# RCJ_OnStage2024_FC_drivers.net
KiCad netlist of a schematic drawn in Altium Designer
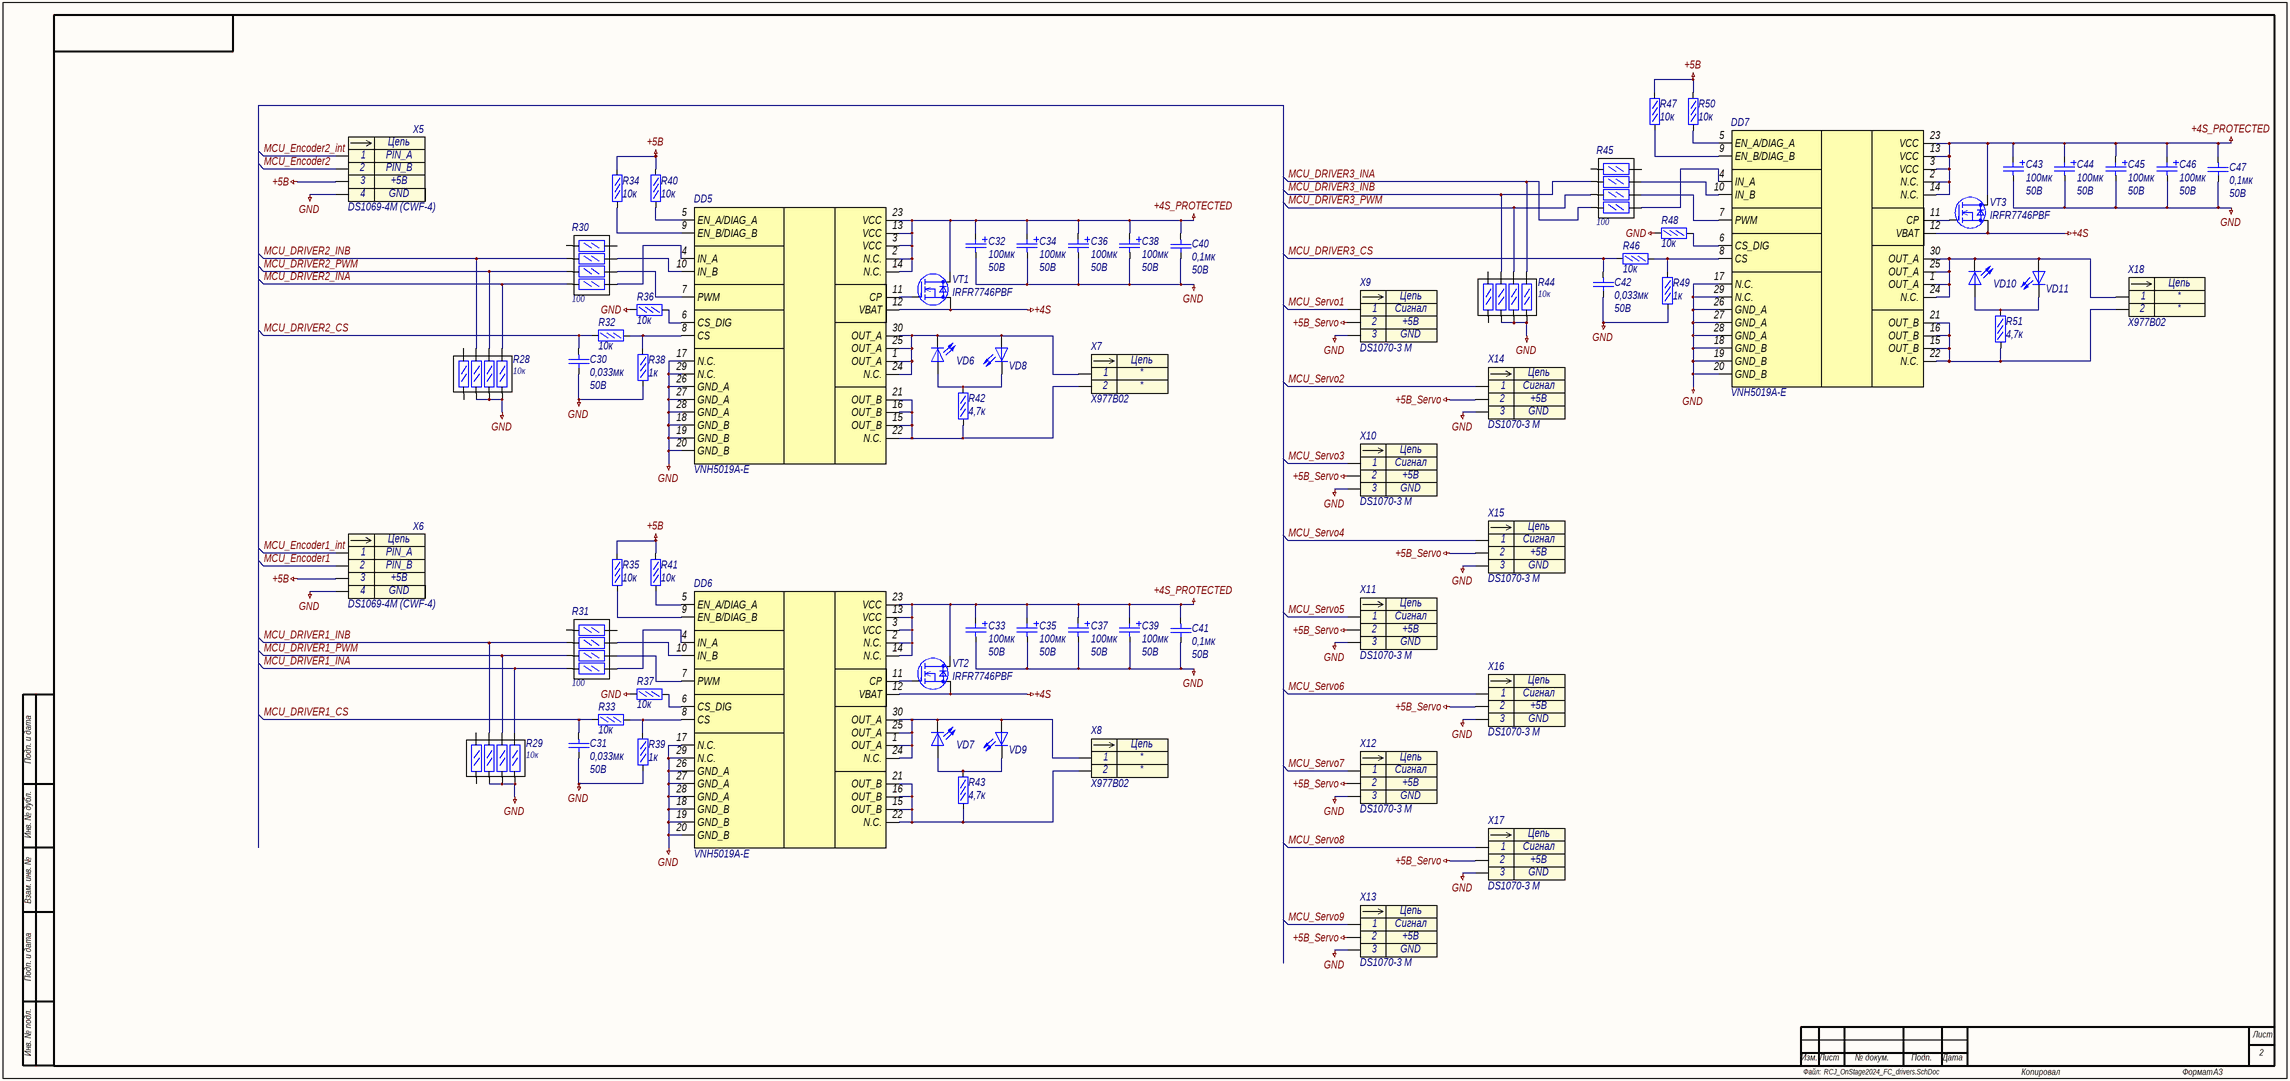
[diagram p0: RCJ_OnStage2024_FC_drivers.SchDoc]

(export (version "E")
  (design (tool "Eeschema 10.0.6"))
  (components
    (comp (ref "C30")
      (value "0,033мк")
      (footprint "C1206")
      (description "Конденсатор кер. 0,033мкФ 50В NP0")
      (fields (field (name "MANUFACTURER") "Murata") (field (name "VOLTAGE") "50В"))
      (libsource (lib "capacitors") (part "GRM3195C1H333J"))
    )
    (comp (ref "C31")
      (value "0,033мк")
      (footprint "C1206")
      (description "Конденсатор кер. 0,033мкФ 50В NP0")
      (fields (field (name "MANUFACTURER") "Murata") (field (name "VOLTAGE") "50В"))
      (libsource (lib "capacitors") (part "GRM3195C1H333J"))
    )
    (comp (ref "C32")
      (value "100мк")
      (footprint "CAPALUM_8x11.5_V")
      (description "Конденсатор эл.лит. алюм. 100мкФ 50В")
      (fields (field (name "MANUFACTURER") "EPCOS") (field (name "VOLTAGE") "50В"))
      (libsource (lib "capacitors") (part "B41858C6107M"))
    )
    (comp (ref "C33")
      (value "100мк")
      (footprint "CAPALUM_8x11.5_V")
      (description "Конденсатор эл.лит. алюм. 100мкФ 50В")
      (fields (field (name "MANUFACTURER") "EPCOS") (field (name "VOLTAGE") "50В"))
      (libsource (lib "capacitors") (part "B41858C6107M"))
    )
    (comp (ref "C34")
      (value "100мк")
      (footprint "CAPALUM_8x11.5_V")
      (description "Конденсатор эл.лит. алюм. 100мкФ 50В")
      (fields (field (name "MANUFACTURER") "EPCOS") (field (name "VOLTAGE") "50В"))
      (libsource (lib "capacitors") (part "B41858C6107M"))
    )
    (comp (ref "C35")
      (value "100мк")
      (footprint "CAPALUM_8x11.5_V")
      (description "Конденсатор эл.лит. алюм. 100мкФ 50В")
      (fields (field (name "MANUFACTURER") "EPCOS") (field (name "VOLTAGE") "50В"))
      (libsource (lib "capacitors") (part "B41858C6107M"))
    )
    (comp (ref "C36")
      (value "100мк")
      (footprint "CAPALUM_8x11.5_V")
      (description "Конденсатор эл.лит. алюм. 100мкФ 50В")
      (fields (field (name "MANUFACTURER") "EPCOS") (field (name "VOLTAGE") "50В"))
      (libsource (lib "capacitors") (part "B41858C6107M"))
    )
    (comp (ref "C37")
      (value "100мк")
      (footprint "CAPALUM_8x11.5_V")
      (description "Конденсатор эл.лит. алюм. 100мкФ 50В")
      (fields (field (name "MANUFACTURER") "EPCOS") (field (name "VOLTAGE") "50В"))
      (libsource (lib "capacitors") (part "B41858C6107M"))
    )
    (comp (ref "C38")
      (value "100мк")
      (footprint "CAPALUM_8x11.5_V")
      (description "Конденсатор эл.лит. алюм. 100мкФ 50В")
      (fields (field (name "MANUFACTURER") "EPCOS") (field (name "VOLTAGE") "50В"))
      (libsource (lib "capacitors") (part "B41858C6107M"))
    )
    (comp (ref "C39")
      (value "100мк")
      (footprint "CAPALUM_8x11.5_V")
      (description "Конденсатор эл.лит. алюм. 100мкФ 50В")
      (fields (field (name "MANUFACTURER") "EPCOS") (field (name "VOLTAGE") "50В"))
      (libsource (lib "capacitors") (part "B41858C6107M"))
    )
    (comp (ref "C40")
      (value "0,1мк")
      (footprint "C0603")
      (description "Конденсатор кер. 0,1мкФ 50В X7R")
      (fields (field (name "MANUFACTURER") "Murata") (field (name "VOLTAGE") "50В"))
      (libsource (lib "capacitors") (part "GRM188R71H104KA93D"))
    )
    (comp (ref "C41")
      (value "0,1мк")
      (footprint "C0603")
      (description "Конденсатор кер. 0,1мкФ 50В X7R")
      (fields (field (name "MANUFACTURER") "Murata") (field (name "VOLTAGE") "50В"))
      (libsource (lib "capacitors") (part "GRM188R71H104KA93D"))
    )
    (comp (ref "C42")
      (value "0,033мк")
      (footprint "C1206")
      (description "Конденсатор кер. 0,033мкФ 50В NP0")
      (fields (field (name "MANUFACTURER") "Murata") (field (name "VOLTAGE") "50В"))
      (libsource (lib "capacitors") (part "GRM3195C1H333J"))
    )
    (comp (ref "C43")
      (value "100мк")
      (footprint "CAPALUM_8x11.5_V")
      (description "Конденсатор эл.лит. алюм. 100мкФ 50В")
      (fields (field (name "MANUFACTURER") "EPCOS") (field (name "VOLTAGE") "50В"))
      (libsource (lib "capacitors") (part "B41858C6107M"))
    )
    (comp (ref "C44")
      (value "100мк")
      (footprint "CAPALUM_8x11.5_V")
      (description "Конденсатор эл.лит. алюм. 100мкФ 50В")
      (fields (field (name "MANUFACTURER") "EPCOS") (field (name "VOLTAGE") "50В"))
      (libsource (lib "capacitors") (part "B41858C6107M"))
    )
    (comp (ref "C45")
      (value "100мк")
      (footprint "CAPALUM_8x11.5_V")
      (description "Конденсатор эл.лит. алюм. 100мкФ 50В")
      (fields (field (name "MANUFACTURER") "EPCOS") (field (name "VOLTAGE") "50В"))
      (libsource (lib "capacitors") (part "B41858C6107M"))
    )
    (comp (ref "C46")
      (value "100мк")
      (footprint "CAPALUM_8x11.5_V")
      (description "Конденсатор эл.лит. алюм. 100мкФ 50В")
      (fields (field (name "MANUFACTURER") "EPCOS") (field (name "VOLTAGE") "50В"))
      (libsource (lib "capacitors") (part "B41858C6107M"))
    )
    (comp (ref "C47")
      (value "0,1мк")
      (footprint "C0603")
      (description "Конденсатор кер. 0,1мкФ 50В X7R")
      (fields (field (name "MANUFACTURER") "Murata") (field (name "VOLTAGE") "50В"))
      (libsource (lib "capacitors") (part "GRM188R71H104KA93D"))
    )
    (comp (ref "DD5") (value "VNH5019A-E") (footprint "SO-30") (libsource (lib "mcu") (part "VNH5019A-E")))
    (comp (ref "DD6") (value "VNH5019A-E") (footprint "SO-30") (libsource (lib "mcu") (part "VNH5019A-E")))
    (comp (ref "DD7") (value "VNH5019A-E") (footprint "SO-30") (libsource (lib "mcu") (part "VNH5019A-E")))
    (comp (ref "R28")
      (value "10к")
      (footprint "R0603x4")
      (description "Резисторы  0,125Вт")
      (libsource (lib "resistors") (part "Резисторная сборка х4 0,125 10кОм"))
    )
    (comp (ref "R29")
      (value "10к")
      (footprint "R0603x4")
      (description "Резисторы  0,125Вт")
      (libsource (lib "resistors") (part "Резисторная сборка х4 0,125 10кОм"))
    )
    (comp (ref "R30")
      (value "100")
      (footprint "R0603x4")
      (description "Резисторы  0,125Вт")
      (libsource (lib "resistors") (part "Резисторная сборка х4 0,125"))
    )
    (comp (ref "R31")
      (value "100")
      (footprint "R0603x4")
      (description "Резисторы  0,125Вт")
      (libsource (lib "resistors") (part "Резисторная сборка х4 0,125"))
    )
    (comp (ref "R32")
      (value "10к")
      (footprint "R0603")
      (description "Резистор 10кОм 0,063Вт 1%")
      (fields (field (name "MANUFACTURER") "YAGEO") (field (name "TOLERANCE") "1%"))
      (libsource (lib "resistors") (part "RC0603FR-0710KL"))
    )
    (comp (ref "R33")
      (value "10к")
      (footprint "R0603")
      (description "Резистор 10кОм 0,063Вт 1%")
      (fields (field (name "MANUFACTURER") "YAGEO") (field (name "TOLERANCE") "1%"))
      (libsource (lib "resistors") (part "RC0603FR-0710KL"))
    )
    (comp (ref "R34")
      (value "10к")
      (footprint "R0603")
      (description "Резистор 10кОм 0,063Вт 1%")
      (fields (field (name "MANUFACTURER") "YAGEO") (field (name "TOLERANCE") "1%"))
      (libsource (lib "") (part "RC0603FR-0710KL_1"))
    )
    (comp (ref "R35")
      (value "10к")
      (footprint "R0603")
      (description "Резистор 10кОм 0,063Вт 1%")
      (fields (field (name "MANUFACTURER") "YAGEO") (field (name "TOLERANCE") "1%"))
      (libsource (lib "") (part "RC0603FR-0710KL_1"))
    )
    (comp (ref "R36")
      (value "10к")
      (footprint "R0603")
      (description "Резистор 10кОм 0,063Вт 1%")
      (fields (field (name "MANUFACTURER") "YAGEO") (field (name "TOLERANCE") "1%"))
      (libsource (lib "resistors") (part "RC0603FR-0710KL"))
    )
    (comp (ref "R37")
      (value "10к")
      (footprint "R0603")
      (description "Резистор 10кОм 0,063Вт 1%")
      (fields (field (name "MANUFACTURER") "YAGEO") (field (name "TOLERANCE") "1%"))
      (libsource (lib "resistors") (part "RC0603FR-0710KL"))
    )
    (comp (ref "R38")
      (value "1к")
      (footprint "R0603")
      (description "Резистор 1кОм 0,063Вт 1%")
      (fields (field (name "MANUFACTURER") "YAGEO") (field (name "TOLERANCE") "1%"))
      (libsource (lib "resistors") (part "RC0603FR-071KL"))
    )
    (comp (ref "R39")
      (value "1к")
      (footprint "R0603")
      (description "Резистор 1кОм 0,063Вт 1%")
      (fields (field (name "MANUFACTURER") "YAGEO") (field (name "TOLERANCE") "1%"))
      (libsource (lib "resistors") (part "RC0603FR-071KL"))
    )
    (comp (ref "R40")
      (value "10к")
      (footprint "R0603")
      (description "Резистор 10кОм 0,063Вт 1%")
      (fields (field (name "MANUFACTURER") "YAGEO") (field (name "TOLERANCE") "1%"))
      (libsource (lib "") (part "RC0603FR-0710KL_1"))
    )
    (comp (ref "R41")
      (value "10к")
      (footprint "R0603")
      (description "Резистор 10кОм 0,063Вт 1%")
      (fields (field (name "MANUFACTURER") "YAGEO") (field (name "TOLERANCE") "1%"))
      (libsource (lib "") (part "RC0603FR-0710KL_1"))
    )
    (comp (ref "R42")
      (value "4,7к")
      (footprint "R0603")
      (description "Резистор 4,7кОм 0,063Вт 1%")
      (fields (field (name "MANUFACTURER") "YAGEO") (field (name "TOLERANCE") "1%"))
      (libsource (lib "resistors") (part "RC0603FR-074K7L"))
    )
    (comp (ref "R43")
      (value "4,7к")
      (footprint "R0603")
      (description "Резистор 4,7кОм 0,063Вт 1%")
      (fields (field (name "MANUFACTURER") "YAGEO") (field (name "TOLERANCE") "1%"))
      (libsource (lib "resistors") (part "RC0603FR-074K7L"))
    )
    (comp (ref "R44")
      (value "10к")
      (footprint "R0603x4")
      (description "Резисторы  0,125Вт")
      (libsource (lib "resistors") (part "Резисторная сборка х4 0,125 10кОм"))
    )
    (comp (ref "R45")
      (value "100")
      (footprint "R0603x4")
      (description "Резисторы  0,125Вт")
      (libsource (lib "resistors") (part "Резисторная сборка х4 0,125"))
    )
    (comp (ref "R46")
      (value "10к")
      (footprint "R0603")
      (description "Резистор 10кОм 0,063Вт 1%")
      (fields (field (name "MANUFACTURER") "YAGEO") (field (name "TOLERANCE") "1%"))
      (libsource (lib "resistors") (part "RC0603FR-0710KL"))
    )
    (comp (ref "R47")
      (value "10к")
      (footprint "R0603")
      (description "Резистор 10кОм 0,063Вт 1%")
      (fields (field (name "MANUFACTURER") "YAGEO") (field (name "TOLERANCE") "1%"))
      (libsource (lib "") (part "RC0603FR-0710KL_1"))
    )
    (comp (ref "R48")
      (value "10к")
      (footprint "R0603")
      (description "Резистор 10кОм 0,063Вт 1%")
      (fields (field (name "MANUFACTURER") "YAGEO") (field (name "TOLERANCE") "1%"))
      (libsource (lib "resistors") (part "RC0603FR-0710KL"))
    )
    (comp (ref "R49")
      (value "1к")
      (footprint "R0603")
      (description "Резистор 1кОм 0,063Вт 1%")
      (fields (field (name "MANUFACTURER") "YAGEO") (field (name "TOLERANCE") "1%"))
      (libsource (lib "resistors") (part "RC0603FR-071KL"))
    )
    (comp (ref "R50")
      (value "10к")
      (footprint "R0603")
      (description "Резистор 10кОм 0,063Вт 1%")
      (fields (field (name "MANUFACTURER") "YAGEO") (field (name "TOLERANCE") "1%"))
      (libsource (lib "") (part "RC0603FR-0710KL_1"))
    )
    (comp (ref "R51")
      (value "4,7к")
      (footprint "R0603")
      (description "Резистор 4,7кОм 0,063Вт 1%")
      (fields (field (name "MANUFACTURER") "YAGEO") (field (name "TOLERANCE") "1%"))
      (libsource (lib "resistors") (part "RC0603FR-074K7L"))
    )
    (comp (ref "VD6")
      (value "~")
      (footprint "LED0603_RED")
      (description "Светодиод")
      (libsource (lib "diodes") (part "LED"))
    )
    (comp (ref "VD7")
      (value "~")
      (footprint "LED0603_RED")
      (description "Светодиод")
      (libsource (lib "diodes") (part "LED"))
    )
    (comp (ref "VD8")
      (value "~")
      (footprint "LED0603_GREEN")
      (description "Светодиод")
      (libsource (lib "diodes") (part "LED"))
    )
    (comp (ref "VD9")
      (value "~")
      (footprint "LED0603_GREEN")
      (description "Светодиод")
      (libsource (lib "diodes") (part "LED"))
    )
    (comp (ref "VD10")
      (value "~")
      (footprint "LED0603_RED")
      (description "Светодиод")
      (libsource (lib "diodes") (part "LED"))
    )
    (comp (ref "VD11")
      (value "~")
      (footprint "LED0603_GREEN")
      (description "Светодиод")
      (libsource (lib "diodes") (part "LED"))
    )
    (comp (ref "VT1")
      (value "IRFR7746PBF")
      (footprint "D-PAK")
      (description "N-MOSFET 75В, 56А")
      (fields (field (name "MANUFACTURER") "Internationa Rectifier"))
      (libsource (lib "transistors") (part "IRFR7746PBF"))
    )
    (comp (ref "VT2")
      (value "IRFR7746PBF")
      (footprint "D-PAK")
      (description "N-MOSFET 75В, 56А")
      (fields (field (name "MANUFACTURER") "Internationa Rectifier"))
      (libsource (lib "transistors") (part "IRFR7746PBF"))
    )
    (comp (ref "VT3")
      (value "IRFR7746PBF")
      (footprint "D-PAK")
      (description "N-MOSFET 75В, 56А")
      (fields (field (name "MANUFACTURER") "Internationa Rectifier"))
      (libsource (lib "transistors") (part "IRFR7746PBF"))
    )
    (comp (ref "X5")
      (value "DS1069-4M (CWF-4)")
      (footprint "CWF-4")
      (description "Разъем - 4 конт. прямая вилка на плату")
      (libsource (lib "connectors") (part "CWF-4"))
    )
    (comp (ref "X6")
      (value "DS1069-4M (CWF-4)")
      (footprint "CWF-4")
      (description "Разъем - 4 конт. прямая вилка на плату")
      (libsource (lib "connectors") (part "CWF-4"))
    )
    (comp (ref "X7")
      (value "X977B02")
      (footprint "DG25C-B-02P")
      (description "Клеммник 2-контактный шаг 7.62мм")
      (libsource (lib "connectors") (part "X977B02"))
    )
    (comp (ref "X8")
      (value "X977B02")
      (footprint "DG25C-B-02P")
      (description "Клеммник 2-контактный шаг 7.62мм")
      (libsource (lib "connectors") (part "X977B02"))
    )
    (comp (ref "X9")
      (value "DS1070-3 M")
      (footprint "DS1070-3")
      (description "Вилка на плату 2.54мм открытая 3pin")
      (libsource (lib "connectors") (part "WF-3"))
    )
    (comp (ref "X10")
      (value "DS1070-3 M")
      (footprint "DS1070-3")
      (description "Вилка на плату 2.54мм открытая 3pin")
      (libsource (lib "connectors") (part "WF-3"))
    )
    (comp (ref "X11")
      (value "DS1070-3 M")
      (footprint "DS1070-3")
      (description "Вилка на плату 2.54мм открытая 3pin")
      (libsource (lib "connectors") (part "WF-3"))
    )
    (comp (ref "X12")
      (value "DS1070-3 M")
      (footprint "DS1070-3")
      (description "Вилка на плату 2.54мм открытая 3pin")
      (libsource (lib "connectors") (part "WF-3"))
    )
    (comp (ref "X13")
      (value "DS1070-3 M")
      (footprint "DS1070-3")
      (description "Вилка на плату 2.54мм открытая 3pin")
      (libsource (lib "connectors") (part "WF-3"))
    )
    (comp (ref "X14")
      (value "DS1070-3 M")
      (footprint "DS1070-3")
      (description "Вилка на плату 2.54мм открытая 3pin")
      (libsource (lib "connectors") (part "WF-3"))
    )
    (comp (ref "X15")
      (value "DS1070-3 M")
      (footprint "DS1070-3")
      (description "Вилка на плату 2.54мм открытая 3pin")
      (libsource (lib "connectors") (part "WF-3"))
    )
    (comp (ref "X16")
      (value "DS1070-3 M")
      (footprint "DS1070-3")
      (description "Вилка на плату 2.54мм открытая 3pin")
      (libsource (lib "connectors") (part "WF-3"))
    )
    (comp (ref "X17")
      (value "DS1070-3 M")
      (footprint "DS1070-3")
      (description "Вилка на плату 2.54мм открытая 3pin")
      (libsource (lib "connectors") (part "WF-3"))
    )
    (comp (ref "X18")
      (value "X977B02")
      (footprint "DG25C-B-02P")
      (description "Клеммник 2-контактный шаг 7.62мм")
      (libsource (lib "connectors") (part "X977B02"))
    )
  )
  (nets
    (net (code "1") (name "+4S") (class "Default")
      (node (ref "DD5") (pin "12") (pinfunction "VBAT_12") (pintype "passive"))
      (node (ref "DD6") (pin "12") (pinfunction "VBAT_12") (pintype "passive"))
      (node (ref "DD7") (pin "12") (pinfunction "VBAT_12") (pintype "passive"))
      (node (ref "VT1") (pin "3") (pinfunction "S_3") (pintype "passive"))
      (node (ref "VT2") (pin "3") (pinfunction "S_3") (pintype "passive"))
      (node (ref "VT3") (pin "3") (pinfunction "S_3") (pintype "passive"))
    )
    (net (code "2") (name "+4S_PROTECTED") (class "Default")
      (node (ref "C32") (pin "1") (pinfunction "1_1") (pintype "passive"))
      (node (ref "C33") (pin "1") (pinfunction "1_1") (pintype "passive"))
      (node (ref "C34") (pin "1") (pinfunction "1_1") (pintype "passive"))
      (node (ref "C35") (pin "1") (pinfunction "1_1") (pintype "passive"))
      (node (ref "C36") (pin "1") (pinfunction "1_1") (pintype "passive"))
      (node (ref "C37") (pin "1") (pinfunction "1_1") (pintype "passive"))
      (node (ref "C38") (pin "1") (pinfunction "1_1") (pintype "passive"))
      (node (ref "C39") (pin "1") (pinfunction "1_1") (pintype "passive"))
      (node (ref "C40") (pin "2") (pinfunction "2_2") (pintype "passive"))
      (node (ref "C41") (pin "2") (pinfunction "2_2") (pintype "passive"))
      (node (ref "C43") (pin "1") (pinfunction "1_1") (pintype "passive"))
      (node (ref "C44") (pin "1") (pinfunction "1_1") (pintype "passive"))
      (node (ref "C45") (pin "1") (pinfunction "1_1") (pintype "passive"))
      (node (ref "C46") (pin "1") (pinfunction "1_1") (pintype "passive"))
      (node (ref "C47") (pin "2") (pinfunction "2_2") (pintype "passive"))
      (node (ref "DD5") (pin "13") (pinfunction "VCC_13") (pintype "passive"))
      (node (ref "DD5") (pin "14") (pinfunction "N.C._14") (pintype "passive"))
      (node (ref "DD5") (pin "2") (pinfunction "N.C._2") (pintype "passive"))
      (node (ref "DD5") (pin "23") (pinfunction "VCC_23") (pintype "passive"))
      (node (ref "DD5") (pin "3") (pinfunction "VCC_3") (pintype "passive"))
      (node (ref "DD6") (pin "13") (pinfunction "VCC_13") (pintype "passive"))
      (node (ref "DD6") (pin "14") (pinfunction "N.C._14") (pintype "passive"))
      (node (ref "DD6") (pin "2") (pinfunction "N.C._2") (pintype "passive"))
      (node (ref "DD6") (pin "23") (pinfunction "VCC_23") (pintype "passive"))
      (node (ref "DD6") (pin "3") (pinfunction "VCC_3") (pintype "passive"))
      (node (ref "DD7") (pin "13") (pinfunction "VCC_13") (pintype "passive"))
      (node (ref "DD7") (pin "14") (pinfunction "N.C._14") (pintype "passive"))
      (node (ref "DD7") (pin "2") (pinfunction "N.C._2") (pintype "passive"))
      (node (ref "DD7") (pin "23") (pinfunction "VCC_23") (pintype "passive"))
      (node (ref "DD7") (pin "3") (pinfunction "VCC_3") (pintype "passive"))
      (node (ref "VT1") (pin "2") (pinfunction "D_2") (pintype "passive"))
      (node (ref "VT2") (pin "2") (pinfunction "D_2") (pintype "passive"))
      (node (ref "VT3") (pin "2") (pinfunction "D_2") (pintype "passive"))
    )
    (net (code "3") (name "+5В") (class "Default")
      (node (ref "R34") (pin "2") (pinfunction "2_2") (pintype "passive"))
      (node (ref "R35") (pin "2") (pinfunction "2_2") (pintype "passive"))
      (node (ref "R40") (pin "2") (pinfunction "2_2") (pintype "passive"))
      (node (ref "R41") (pin "2") (pinfunction "2_2") (pintype "passive"))
      (node (ref "R47") (pin "2") (pinfunction "2_2") (pintype "passive"))
      (node (ref "R50") (pin "2") (pinfunction "2_2") (pintype "passive"))
      (node (ref "X5") (pin "3") (pinfunction "3_3") (pintype "passive"))
      (node (ref "X6") (pin "3") (pinfunction "3_3") (pintype "passive"))
    )
    (net (code "4") (name "+5В_Servo") (class "Default")
      (node (ref "X10") (pin "2") (pinfunction "2_2") (pintype "passive"))
      (node (ref "X11") (pin "2") (pinfunction "2_2") (pintype "passive"))
      (node (ref "X12") (pin "2") (pinfunction "2_2") (pintype "passive"))
      (node (ref "X13") (pin "2") (pinfunction "2_2") (pintype "passive"))
      (node (ref "X14") (pin "2") (pinfunction "2_2") (pintype "passive"))
      (node (ref "X15") (pin "2") (pinfunction "2_2") (pintype "passive"))
      (node (ref "X16") (pin "2") (pinfunction "2_2") (pintype "passive"))
      (node (ref "X17") (pin "2") (pinfunction "2_2") (pintype "passive"))
      (node (ref "X9") (pin "2") (pinfunction "2_2") (pintype "passive"))
    )
    (net (code "5") (name "/MCU_DRIVER1_CS") (class "Default")
      (node (ref "C31") (pin "2") (pinfunction "2_2") (pintype "passive"))
      (node (ref "R33") (pin "1") (pinfunction "1_1") (pintype "passive"))
    )
    (net (code "6") (name "/MCU_DRIVER1_INA") (class "Default")
      (node (ref "R29") (pin "8") (pinfunction "8_8") (pintype "passive"))
      (node (ref "R31") (pin "7") (pinfunction "7_7") (pintype "passive"))
    )
    (net (code "7") (name "/MCU_DRIVER1_INB") (class "Default")
      (node (ref "R29") (pin "4") (pinfunction "4_4") (pintype "passive"))
      (node (ref "R31") (pin "3") (pinfunction "3_3") (pintype "passive"))
    )
    (net (code "8") (name "/MCU_DRIVER1_PWM") (class "Default")
      (node (ref "R29") (pin "6") (pinfunction "6_6") (pintype "passive"))
      (node (ref "R31") (pin "5") (pinfunction "5_5") (pintype "passive"))
    )
    (net (code "9") (name "/MCU_DRIVER2_CS") (class "Default")
      (node (ref "C30") (pin "2") (pinfunction "2_2") (pintype "passive"))
      (node (ref "R32") (pin "1") (pinfunction "1_1") (pintype "passive"))
    )
    (net (code "10") (name "/MCU_DRIVER2_INA") (class "Default")
      (node (ref "R28") (pin "8") (pinfunction "8_8") (pintype "passive"))
      (node (ref "R30") (pin "7") (pinfunction "7_7") (pintype "passive"))
    )
    (net (code "11") (name "/MCU_DRIVER2_INB") (class "Default")
      (node (ref "R28") (pin "4") (pinfunction "4_4") (pintype "passive"))
      (node (ref "R30") (pin "3") (pinfunction "3_3") (pintype "passive"))
    )
    (net (code "12") (name "/MCU_DRIVER2_PWM") (class "Default")
      (node (ref "R28") (pin "6") (pinfunction "6_6") (pintype "passive"))
      (node (ref "R30") (pin "5") (pinfunction "5_5") (pintype "passive"))
    )
    (net (code "13") (name "/MCU_DRIVER3_CS") (class "Default")
      (node (ref "C42") (pin "2") (pinfunction "2_2") (pintype "passive"))
      (node (ref "R46") (pin "1") (pinfunction "1_1") (pintype "passive"))
    )
    (net (code "14") (name "/MCU_DRIVER3_INA") (class "Default")
      (node (ref "R44") (pin "8") (pinfunction "8_8") (pintype "passive"))
      (node (ref "R45") (pin "7") (pinfunction "7_7") (pintype "passive"))
    )
    (net (code "15") (name "/MCU_DRIVER3_INB") (class "Default")
      (node (ref "R44") (pin "4") (pinfunction "4_4") (pintype "passive"))
      (node (ref "R45") (pin "3") (pinfunction "3_3") (pintype "passive"))
    )
    (net (code "16") (name "/MCU_DRIVER3_PWM") (class "Default")
      (node (ref "R44") (pin "6") (pinfunction "6_6") (pintype "passive"))
      (node (ref "R45") (pin "5") (pinfunction "5_5") (pintype "passive"))
    )
    (net (code "17") (name "/MCU_Encoder1") (class "Default")
      (node (ref "X6") (pin "2") (pinfunction "2_2") (pintype "passive"))
    )
    (net (code "18") (name "/MCU_Encoder1_int") (class "Default")
      (node (ref "X6") (pin "1") (pinfunction "1_1") (pintype "passive"))
    )
    (net (code "19") (name "/MCU_Encoder2") (class "Default")
      (node (ref "X5") (pin "2") (pinfunction "2_2") (pintype "passive"))
    )
    (net (code "20") (name "/MCU_Encoder2_int") (class "Default")
      (node (ref "X5") (pin "1") (pinfunction "1_1") (pintype "passive"))
    )
    (net (code "21") (name "/MCU_Servo1") (class "Default")
      (node (ref "X9") (pin "1") (pinfunction "1_1") (pintype "passive"))
    )
    (net (code "22") (name "/MCU_Servo2") (class "Default")
      (node (ref "X14") (pin "1") (pinfunction "1_1") (pintype "passive"))
    )
    (net (code "23") (name "/MCU_Servo3") (class "Default")
      (node (ref "X10") (pin "1") (pinfunction "1_1") (pintype "passive"))
    )
    (net (code "24") (name "/MCU_Servo4") (class "Default")
      (node (ref "X15") (pin "1") (pinfunction "1_1") (pintype "passive"))
    )
    (net (code "25") (name "/MCU_Servo5") (class "Default")
      (node (ref "X11") (pin "1") (pinfunction "1_1") (pintype "passive"))
    )
    (net (code "26") (name "/MCU_Servo6") (class "Default")
      (node (ref "X16") (pin "1") (pinfunction "1_1") (pintype "passive"))
    )
    (net (code "27") (name "/MCU_Servo7") (class "Default")
      (node (ref "X12") (pin "1") (pinfunction "1_1") (pintype "passive"))
    )
    (net (code "28") (name "/MCU_Servo8") (class "Default")
      (node (ref "X17") (pin "1") (pinfunction "1_1") (pintype "passive"))
    )
    (net (code "29") (name "/MCU_Servo9") (class "Default")
      (node (ref "X13") (pin "1") (pinfunction "1_1") (pintype "passive"))
    )
    (net (code "30") (name "GND") (class "Default")
      (node (ref "C30") (pin "1") (pinfunction "1_1") (pintype "passive"))
      (node (ref "C31") (pin "1") (pinfunction "1_1") (pintype "passive"))
      (node (ref "C32") (pin "2") (pinfunction "2_2") (pintype "passive"))
      (node (ref "C33") (pin "2") (pinfunction "2_2") (pintype "passive"))
      (node (ref "C34") (pin "2") (pinfunction "2_2") (pintype "passive"))
      (node (ref "C35") (pin "2") (pinfunction "2_2") (pintype "passive"))
      (node (ref "C36") (pin "2") (pinfunction "2_2") (pintype "passive"))
      (node (ref "C37") (pin "2") (pinfunction "2_2") (pintype "passive"))
      (node (ref "C38") (pin "2") (pinfunction "2_2") (pintype "passive"))
      (node (ref "C39") (pin "2") (pinfunction "2_2") (pintype "passive"))
      (node (ref "C40") (pin "1") (pinfunction "1_1") (pintype "passive"))
      (node (ref "C41") (pin "1") (pinfunction "1_1") (pintype "passive"))
      (node (ref "C42") (pin "1") (pinfunction "1_1") (pintype "passive"))
      (node (ref "C43") (pin "2") (pinfunction "2_2") (pintype "passive"))
      (node (ref "C44") (pin "2") (pinfunction "2_2") (pintype "passive"))
      (node (ref "C45") (pin "2") (pinfunction "2_2") (pintype "passive"))
      (node (ref "C46") (pin "2") (pinfunction "2_2") (pintype "passive"))
      (node (ref "C47") (pin "1") (pinfunction "1_1") (pintype "passive"))
      (node (ref "DD5") (pin "17") (pinfunction "N.C._17") (pintype "passive"))
      (node (ref "DD5") (pin "18") (pinfunction "GND_B_18") (pintype "passive"))
      (node (ref "DD5") (pin "19") (pinfunction "GND_B_19") (pintype "passive"))
      (node (ref "DD5") (pin "20") (pinfunction "GND_B_20") (pintype "passive"))
      (node (ref "DD5") (pin "26") (pinfunction "GND_A_26") (pintype "passive"))
      (node (ref "DD5") (pin "27") (pinfunction "GND_A_27") (pintype "passive"))
      (node (ref "DD5") (pin "28") (pinfunction "GND_A_28") (pintype "passive"))
      (node (ref "DD5") (pin "29") (pinfunction "N.C._29") (pintype "passive"))
      (node (ref "DD6") (pin "17") (pinfunction "N.C._17") (pintype "passive"))
      (node (ref "DD6") (pin "18") (pinfunction "GND_B_18") (pintype "passive"))
      (node (ref "DD6") (pin "19") (pinfunction "GND_B_19") (pintype "passive"))
      (node (ref "DD6") (pin "20") (pinfunction "GND_B_20") (pintype "passive"))
      (node (ref "DD6") (pin "26") (pinfunction "GND_A_26") (pintype "passive"))
      (node (ref "DD6") (pin "27") (pinfunction "GND_A_27") (pintype "passive"))
      (node (ref "DD6") (pin "28") (pinfunction "GND_A_28") (pintype "passive"))
      (node (ref "DD6") (pin "29") (pinfunction "N.C._29") (pintype "passive"))
      (node (ref "DD7") (pin "17") (pinfunction "N.C._17") (pintype "passive"))
      (node (ref "DD7") (pin "18") (pinfunction "GND_B_18") (pintype "passive"))
      (node (ref "DD7") (pin "19") (pinfunction "GND_B_19") (pintype "passive"))
      (node (ref "DD7") (pin "20") (pinfunction "GND_B_20") (pintype "passive"))
      (node (ref "DD7") (pin "26") (pinfunction "GND_A_26") (pintype "passive"))
      (node (ref "DD7") (pin "27") (pinfunction "GND_A_27") (pintype "passive"))
      (node (ref "DD7") (pin "28") (pinfunction "GND_A_28") (pintype "passive"))
      (node (ref "DD7") (pin "29") (pinfunction "N.C._29") (pintype "passive"))
      (node (ref "R28") (pin "3") (pinfunction "3_3") (pintype "passive"))
      (node (ref "R28") (pin "5") (pinfunction "5_5") (pintype "passive"))
      (node (ref "R28") (pin "7") (pinfunction "7_7") (pintype "passive"))
      (node (ref "R29") (pin "3") (pinfunction "3_3") (pintype "passive"))
      (node (ref "R29") (pin "5") (pinfunction "5_5") (pintype "passive"))
      (node (ref "R29") (pin "7") (pinfunction "7_7") (pintype "passive"))
      (node (ref "R36") (pin "1") (pinfunction "1_1") (pintype "passive"))
      (node (ref "R37") (pin "1") (pinfunction "1_1") (pintype "passive"))
      (node (ref "R38") (pin "1") (pinfunction "1_1") (pintype "passive"))
      (node (ref "R39") (pin "1") (pinfunction "1_1") (pintype "passive"))
      (node (ref "R44") (pin "3") (pinfunction "3_3") (pintype "passive"))
      (node (ref "R44") (pin "5") (pinfunction "5_5") (pintype "passive"))
      (node (ref "R44") (pin "7") (pinfunction "7_7") (pintype "passive"))
      (node (ref "R48") (pin "1") (pinfunction "1_1") (pintype "passive"))
      (node (ref "R49") (pin "1") (pinfunction "1_1") (pintype "passive"))
      (node (ref "X10") (pin "3") (pinfunction "3_3") (pintype "passive"))
      (node (ref "X11") (pin "3") (pinfunction "3_3") (pintype "passive"))
      (node (ref "X12") (pin "3") (pinfunction "3_3") (pintype "passive"))
      (node (ref "X13") (pin "3") (pinfunction "3_3") (pintype "passive"))
      (node (ref "X14") (pin "3") (pinfunction "3_3") (pintype "passive"))
      (node (ref "X15") (pin "3") (pinfunction "3_3") (pintype "passive"))
      (node (ref "X16") (pin "3") (pinfunction "3_3") (pintype "passive"))
      (node (ref "X17") (pin "3") (pinfunction "3_3") (pintype "passive"))
      (node (ref "X5") (pin "4") (pinfunction "4_4") (pintype "passive"))
      (node (ref "X6") (pin "4") (pinfunction "4_4") (pintype "passive"))
      (node (ref "X9") (pin "3") (pinfunction "3_3") (pintype "passive"))
    )
    (net (code "31") (name "Net-(DD5-CP)") (class "Default")
      (node (ref "DD5") (pin "11") (pinfunction "CP_11") (pintype "passive"))
      (node (ref "VT1") (pin "1") (pinfunction "G_1") (pintype "passive"))
    )
    (net (code "32") (name "Net-(DD5-CS)") (class "Default")
      (node (ref "DD5") (pin "8") (pinfunction "CS_8") (pintype "passive"))
      (node (ref "R32") (pin "2") (pinfunction "2_2") (pintype "passive"))
      (node (ref "R38") (pin "2") (pinfunction "2_2") (pintype "passive"))
    )
    (net (code "33") (name "Net-(DD5-CS_DIG)") (class "Default")
      (node (ref "DD5") (pin "6") (pinfunction "CS_DIG_6") (pintype "passive"))
      (node (ref "R36") (pin "2") (pinfunction "2_2") (pintype "passive"))
    )
    (net (code "34") (name "Net-(DD5-EN_A{slash}DIAG_A)") (class "Default")
      (node (ref "DD5") (pin "5") (pinfunction "EN_A/DIAG_A_5") (pintype "passive"))
      (node (ref "R40") (pin "1") (pinfunction "1_1") (pintype "passive"))
    )
    (net (code "35") (name "Net-(DD5-EN_B{slash}DIAG_B)") (class "Default")
      (node (ref "DD5") (pin "9") (pinfunction "EN_B/DIAG_B_9") (pintype "passive"))
      (node (ref "R34") (pin "1") (pinfunction "1_1") (pintype "passive"))
    )
    (net (code "36") (name "Net-(DD5-IN_A)") (class "Default")
      (node (ref "DD5") (pin "4") (pinfunction "IN_A_4") (pintype "passive"))
      (node (ref "R30") (pin "8") (pinfunction "8_8") (pintype "passive"))
    )
    (net (code "37") (name "Net-(DD5-IN_B)") (class "Default")
      (node (ref "DD5") (pin "10") (pinfunction "IN_B_10") (pintype "passive"))
      (node (ref "R30") (pin "4") (pinfunction "4_4") (pintype "passive"))
    )
    (net (code "38") (name "Net-(DD5-N.C.-Pad22)") (class "Default")
      (node (ref "DD5") (pin "15") (pinfunction "OUT_B_15") (pintype "passive"))
      (node (ref "DD5") (pin "16") (pinfunction "OUT_B_16") (pintype "passive"))
      (node (ref "DD5") (pin "21") (pinfunction "OUT_B_21") (pintype "passive"))
      (node (ref "DD5") (pin "22") (pinfunction "N.C._22") (pintype "passive"))
      (node (ref "R42") (pin "2") (pinfunction "2_2") (pintype "passive"))
      (node (ref "X7") (pin "2") (pinfunction "2_2") (pintype "passive"))
    )
    (net (code "39") (name "Net-(DD5-PWM)") (class "Default")
      (node (ref "DD5") (pin "7") (pinfunction "PWM_7") (pintype "passive"))
      (node (ref "R30") (pin "6") (pinfunction "6_6") (pintype "passive"))
    )
    (net (code "40") (name "Net-(DD6-CP)") (class "Default")
      (node (ref "DD6") (pin "11") (pinfunction "CP_11") (pintype "passive"))
      (node (ref "VT2") (pin "1") (pinfunction "G_1") (pintype "passive"))
    )
    (net (code "41") (name "Net-(DD6-CS)") (class "Default")
      (node (ref "DD6") (pin "8") (pinfunction "CS_8") (pintype "passive"))
      (node (ref "R33") (pin "2") (pinfunction "2_2") (pintype "passive"))
      (node (ref "R39") (pin "2") (pinfunction "2_2") (pintype "passive"))
    )
    (net (code "42") (name "Net-(DD6-CS_DIG)") (class "Default")
      (node (ref "DD6") (pin "6") (pinfunction "CS_DIG_6") (pintype "passive"))
      (node (ref "R37") (pin "2") (pinfunction "2_2") (pintype "passive"))
    )
    (net (code "43") (name "Net-(DD6-EN_A{slash}DIAG_A)") (class "Default")
      (node (ref "DD6") (pin "5") (pinfunction "EN_A/DIAG_A_5") (pintype "passive"))
      (node (ref "R41") (pin "1") (pinfunction "1_1") (pintype "passive"))
    )
    (net (code "44") (name "Net-(DD6-EN_B{slash}DIAG_B)") (class "Default")
      (node (ref "DD6") (pin "9") (pinfunction "EN_B/DIAG_B_9") (pintype "passive"))
      (node (ref "R35") (pin "1") (pinfunction "1_1") (pintype "passive"))
    )
    (net (code "45") (name "Net-(DD6-IN_A)") (class "Default")
      (node (ref "DD6") (pin "4") (pinfunction "IN_A_4") (pintype "passive"))
      (node (ref "R31") (pin "8") (pinfunction "8_8") (pintype "passive"))
    )
    (net (code "46") (name "Net-(DD6-IN_B)") (class "Default")
      (node (ref "DD6") (pin "10") (pinfunction "IN_B_10") (pintype "passive"))
      (node (ref "R31") (pin "4") (pinfunction "4_4") (pintype "passive"))
    )
    (net (code "47") (name "Net-(DD6-N.C.-Pad22)") (class "Default")
      (node (ref "DD6") (pin "15") (pinfunction "OUT_B_15") (pintype "passive"))
      (node (ref "DD6") (pin "16") (pinfunction "OUT_B_16") (pintype "passive"))
      (node (ref "DD6") (pin "21") (pinfunction "OUT_B_21") (pintype "passive"))
      (node (ref "DD6") (pin "22") (pinfunction "N.C._22") (pintype "passive"))
      (node (ref "R43") (pin "2") (pinfunction "2_2") (pintype "passive"))
      (node (ref "X8") (pin "2") (pinfunction "2_2") (pintype "passive"))
    )
    (net (code "48") (name "Net-(DD6-PWM)") (class "Default")
      (node (ref "DD6") (pin "7") (pinfunction "PWM_7") (pintype "passive"))
      (node (ref "R31") (pin "6") (pinfunction "6_6") (pintype "passive"))
    )
    (net (code "49") (name "Net-(DD7-CP)") (class "Default")
      (node (ref "DD7") (pin "11") (pinfunction "CP_11") (pintype "passive"))
      (node (ref "VT3") (pin "1") (pinfunction "G_1") (pintype "passive"))
    )
    (net (code "50") (name "Net-(DD7-CS)") (class "Default")
      (node (ref "DD7") (pin "8") (pinfunction "CS_8") (pintype "passive"))
      (node (ref "R46") (pin "2") (pinfunction "2_2") (pintype "passive"))
      (node (ref "R49") (pin "2") (pinfunction "2_2") (pintype "passive"))
    )
    (net (code "51") (name "Net-(DD7-CS_DIG)") (class "Default")
      (node (ref "DD7") (pin "6") (pinfunction "CS_DIG_6") (pintype "passive"))
      (node (ref "R48") (pin "2") (pinfunction "2_2") (pintype "passive"))
    )
    (net (code "52") (name "Net-(DD7-EN_A{slash}DIAG_A)") (class "Default")
      (node (ref "DD7") (pin "5") (pinfunction "EN_A/DIAG_A_5") (pintype "passive"))
      (node (ref "R50") (pin "1") (pinfunction "1_1") (pintype "passive"))
    )
    (net (code "53") (name "Net-(DD7-EN_B{slash}DIAG_B)") (class "Default")
      (node (ref "DD7") (pin "9") (pinfunction "EN_B/DIAG_B_9") (pintype "passive"))
      (node (ref "R47") (pin "1") (pinfunction "1_1") (pintype "passive"))
    )
    (net (code "54") (name "Net-(DD7-IN_A)") (class "Default")
      (node (ref "DD7") (pin "4") (pinfunction "IN_A_4") (pintype "passive"))
      (node (ref "R45") (pin "8") (pinfunction "8_8") (pintype "passive"))
    )
    (net (code "55") (name "Net-(DD7-IN_B)") (class "Default")
      (node (ref "DD7") (pin "10") (pinfunction "IN_B_10") (pintype "passive"))
      (node (ref "R45") (pin "4") (pinfunction "4_4") (pintype "passive"))
    )
    (net (code "56") (name "Net-(DD7-N.C.-Pad22)") (class "Default")
      (node (ref "DD7") (pin "15") (pinfunction "OUT_B_15") (pintype "passive"))
      (node (ref "DD7") (pin "16") (pinfunction "OUT_B_16") (pintype "passive"))
      (node (ref "DD7") (pin "21") (pinfunction "OUT_B_21") (pintype "passive"))
      (node (ref "DD7") (pin "22") (pinfunction "N.C._22") (pintype "passive"))
      (node (ref "R51") (pin "2") (pinfunction "2_2") (pintype "passive"))
      (node (ref "X18") (pin "2") (pinfunction "2_2") (pintype "passive"))
    )
    (net (code "57") (name "Net-(DD7-PWM)") (class "Default")
      (node (ref "DD7") (pin "7") (pinfunction "PWM_7") (pintype "passive"))
      (node (ref "R45") (pin "6") (pinfunction "6_6") (pintype "passive"))
    )
    (net (code "58") (name "Net-(VD6-A)") (class "Default")
      (node (ref "R42") (pin "1") (pinfunction "1_1") (pintype "passive"))
      (node (ref "VD6") (pin "2") (pinfunction "A_2") (pintype "passive"))
      (node (ref "VD8") (pin "1") (pinfunction "K_1") (pintype "passive"))
    )
    (net (code "59") (name "Net-(VD6-K)") (class "Default")
      (node (ref "DD5") (pin "1") (pinfunction "OUT_A_1") (pintype "passive"))
      (node (ref "DD5") (pin "24") (pinfunction "N.C._24") (pintype "passive"))
      (node (ref "DD5") (pin "25") (pinfunction "OUT_A_25") (pintype "passive"))
      (node (ref "DD5") (pin "30") (pinfunction "OUT_A_30") (pintype "passive"))
      (node (ref "VD6") (pin "1") (pinfunction "K_1") (pintype "passive"))
      (node (ref "VD8") (pin "2") (pinfunction "A_2") (pintype "passive"))
      (node (ref "X7") (pin "1") (pinfunction "1_1") (pintype "passive"))
    )
    (net (code "60") (name "Net-(VD7-A)") (class "Default")
      (node (ref "R43") (pin "1") (pinfunction "1_1") (pintype "passive"))
      (node (ref "VD7") (pin "2") (pinfunction "A_2") (pintype "passive"))
      (node (ref "VD9") (pin "1") (pinfunction "K_1") (pintype "passive"))
    )
    (net (code "61") (name "Net-(VD7-K)") (class "Default")
      (node (ref "DD6") (pin "1") (pinfunction "OUT_A_1") (pintype "passive"))
      (node (ref "DD6") (pin "24") (pinfunction "N.C._24") (pintype "passive"))
      (node (ref "DD6") (pin "25") (pinfunction "OUT_A_25") (pintype "passive"))
      (node (ref "DD6") (pin "30") (pinfunction "OUT_A_30") (pintype "passive"))
      (node (ref "VD7") (pin "1") (pinfunction "K_1") (pintype "passive"))
      (node (ref "VD9") (pin "2") (pinfunction "A_2") (pintype "passive"))
      (node (ref "X8") (pin "1") (pinfunction "1_1") (pintype "passive"))
    )
    (net (code "62") (name "Net-(VD10-A)") (class "Default")
      (node (ref "R51") (pin "1") (pinfunction "1_1") (pintype "passive"))
      (node (ref "VD10") (pin "2") (pinfunction "A_2") (pintype "passive"))
      (node (ref "VD11") (pin "1") (pinfunction "K_1") (pintype "passive"))
    )
    (net (code "63") (name "Net-(VD10-K)") (class "Default")
      (node (ref "DD7") (pin "1") (pinfunction "OUT_A_1") (pintype "passive"))
      (node (ref "DD7") (pin "24") (pinfunction "N.C._24") (pintype "passive"))
      (node (ref "DD7") (pin "25") (pinfunction "OUT_A_25") (pintype "passive"))
      (node (ref "DD7") (pin "30") (pinfunction "OUT_A_30") (pintype "passive"))
      (node (ref "VD10") (pin "1") (pinfunction "K_1") (pintype "passive"))
      (node (ref "VD11") (pin "2") (pinfunction "A_2") (pintype "passive"))
      (node (ref "X18") (pin "1") (pinfunction "1_1") (pintype "passive"))
    )
    (net (code "64") (name "unconnected-(R28-Pad1)") (class "Default")
      (node (ref "R28") (pin "1") (pinfunction "1_1") (pintype "passive"))
    )
    (net (code "65") (name "unconnected-(R28-Pad2)") (class "Default")
      (node (ref "R28") (pin "2") (pinfunction "2_2") (pintype "passive"))
    )
    (net (code "66") (name "unconnected-(R29-Pad1)") (class "Default")
      (node (ref "R29") (pin "1") (pinfunction "1_1") (pintype "passive"))
    )
    (net (code "67") (name "unconnected-(R29-Pad2)") (class "Default")
      (node (ref "R29") (pin "2") (pinfunction "2_2") (pintype "passive"))
    )
    (net (code "68") (name "unconnected-(R30-Pad1)") (class "Default")
      (node (ref "R30") (pin "1") (pinfunction "1_1") (pintype "passive"))
    )
    (net (code "69") (name "unconnected-(R30-Pad2)") (class "Default")
      (node (ref "R30") (pin "2") (pinfunction "2_2") (pintype "passive"))
    )
    (net (code "70") (name "unconnected-(R31-Pad1)") (class "Default")
      (node (ref "R31") (pin "1") (pinfunction "1_1") (pintype "passive"))
    )
    (net (code "71") (name "unconnected-(R31-Pad2)") (class "Default")
      (node (ref "R31") (pin "2") (pinfunction "2_2") (pintype "passive"))
    )
    (net (code "72") (name "unconnected-(R44-Pad1)") (class "Default")
      (node (ref "R44") (pin "1") (pinfunction "1_1") (pintype "passive"))
    )
    (net (code "73") (name "unconnected-(R44-Pad2)") (class "Default")
      (node (ref "R44") (pin "2") (pinfunction "2_2") (pintype "passive"))
    )
    (net (code "74") (name "unconnected-(R45-Pad1)") (class "Default")
      (node (ref "R45") (pin "1") (pinfunction "1_1") (pintype "passive"))
    )
    (net (code "75") (name "unconnected-(R45-Pad2)") (class "Default")
      (node (ref "R45") (pin "2") (pinfunction "2_2") (pintype "passive"))
    )
  )
)
